# untitled.net
KiCad netlist of a schematic drawn in EAGLE
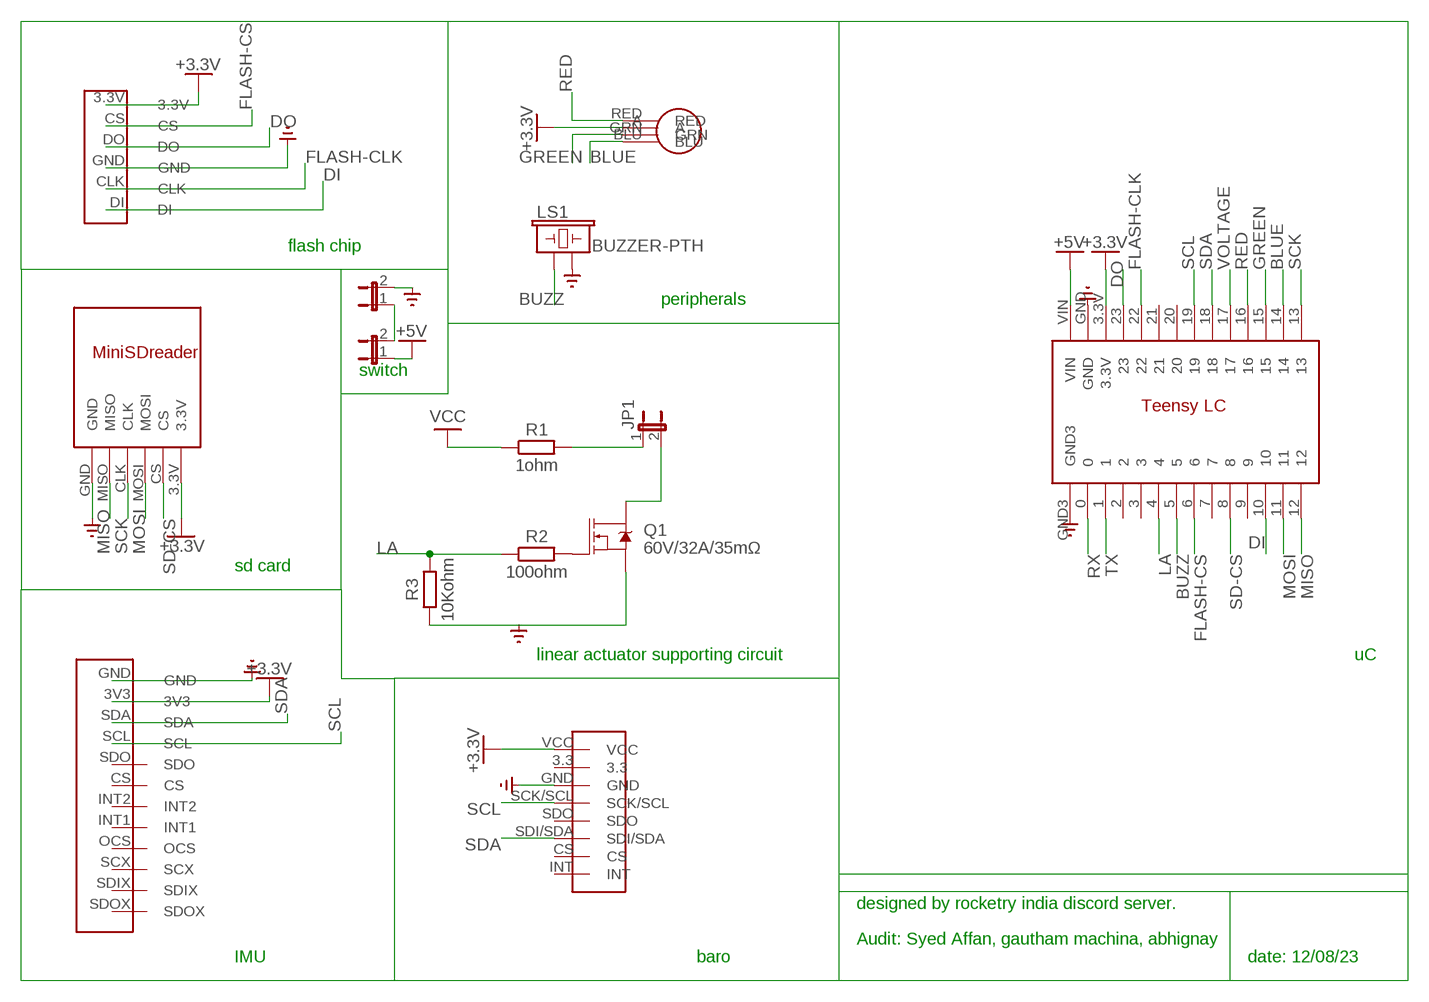
[diagram p0: schematic, sheet 1]

(export (version "E")
  (design (tool "Eeschema 10.0.6"))
  (components
    (comp (ref "JP1")
      (value "JP1E")
      (footprint "eagle-import:JP1")
      (libsource (lib "eagle-import") (part "JP1E"))
    )
    (comp (ref "JP2")
      (value "JP1E")
      (footprint "eagle-import:JP1")
      (libsource (lib "eagle-import") (part "JP1E"))
    )
    (comp (ref "JP3")
      (value "JP1E")
      (footprint "eagle-import:JP1")
      (libsource (lib "eagle-import") (part "JP1E"))
    )
    (comp (ref "LS1")
      (value "BUZZER-PTH")
      (footprint "eagle-import:BUZZER-12MM")
      (libsource (lib "eagle-import") (part "BUZZER-PTH"))
    )
    (comp (ref "Q1")
      (value "60V/32A/35mΩ")
      (footprint "eagle-import:TO220V")
      (libsource (lib "eagle-import") (part "MOSFET-NCH-FQP30N06L"))
    )
    (comp (ref "R1")
      (value "1ohm")
      (footprint "eagle-import:RESAD724W46L381D178B")
      (libsource (lib "eagle-import") (part "RAXIAL-7.2MM-PITCH_"))
    )
    (comp (ref "R2")
      (value "100ohm")
      (footprint "eagle-import:RESAD724W46L381D178B")
      (libsource (lib "eagle-import") (part "RAXIAL-7.2MM-PITCH_"))
    )
    (comp (ref "R3")
      (value "10Kohm")
      (footprint "eagle-import:RESAD724W46L381D178B")
      (libsource (lib "eagle-import") (part "RAXIAL-7.2MM-PITCH_"))
    )
    (comp (ref "U$1")
      (value "TEENSYLC")
      (footprint "eagle-import:TEENSYLC")
      (libsource (lib "eagle-import") (part "TEENSYLC"))
    )
    (comp (ref "U$2")
      (value "LED")
      (footprint "eagle-import:LED")
      (libsource (lib "eagle-import") (part "LED"))
    )
    (comp (ref "U$3")
      (value "FLASH")
      (footprint "eagle-import:FLASH")
      (libsource (lib "eagle-import") (part "FLASH"))
    )
    (comp (ref "U$4")
      (value "MINISDREADER")
      (footprint "eagle-import:MINISDREADER")
      (libsource (lib "eagle-import") (part "MINISDREADER"))
    )
    (comp (ref "U$5")
      (value "LSM6DSO")
      (footprint "eagle-import:LSM6DSO")
      (libsource (lib "eagle-import") (part "LSM6DSO"))
    )
    (comp (ref "U$6")
      (value "BMP390")
      (footprint "eagle-import:BMP390")
      (libsource (lib "eagle-import") (part "BMP390"))
    )
  )
  (nets
    (net (code "1") (name "+3.3V") (class "Default")
      (node (ref "U$1") (pin "3.3V") (pinfunction "3.3V_3.3V") (pintype "bidirectional"))
      (node (ref "U$2") (pin "A") (pinfunction "A_A") (pintype "bidirectional"))
      (node (ref "U$3") (pin "3.3V") (pinfunction "3.3V_3.3V") (pintype "bidirectional"))
      (node (ref "U$4") (pin "3.3V") (pinfunction "3.3V_3.3V") (pintype "bidirectional"))
      (node (ref "U$5") (pin "3V3") (pinfunction "3V3_3V3") (pintype "bidirectional"))
      (node (ref "U$6") (pin "VCC") (pinfunction "VCC_VCC") (pintype "bidirectional"))
    )
    (net (code "2") (name "+5V") (class "Default")
      (node (ref "JP3") (pin "1") (pinfunction "1_1") (pintype "passive"))
      (node (ref "U$1") (pin "VIN") (pinfunction "VIN_VIN") (pintype "bidirectional"))
    )
    (net (code "3") (name "/BLUE") (class "Default")
      (node (ref "U$1") (pin "14") (pinfunction "14_14") (pintype "bidirectional"))
      (node (ref "U$2") (pin "BLU") (pinfunction "BLU_BLU") (pintype "bidirectional"))
    )
    (net (code "4") (name "/BUZZ") (class "Default")
      (node (ref "LS1") (pin "+") (pinfunction "1_+") (pintype "passive"))
      (node (ref "U$1") (pin "5") (pinfunction "5_5") (pintype "bidirectional"))
    )
    (net (code "5") (name "/DI") (class "Default")
      (node (ref "U$1") (pin "10") (pinfunction "10_10") (pintype "bidirectional"))
      (node (ref "U$3") (pin "DI") (pinfunction "DI_DI") (pintype "bidirectional"))
    )
    (net (code "6") (name "/DO") (class "Default")
      (node (ref "U$1") (pin "23") (pinfunction "23_23") (pintype "bidirectional"))
      (node (ref "U$3") (pin "DO") (pinfunction "DO_DO") (pintype "bidirectional"))
    )
    (net (code "7") (name "/FLASH-CLK") (class "Default")
      (node (ref "U$1") (pin "22") (pinfunction "22_22") (pintype "bidirectional"))
      (node (ref "U$3") (pin "CLK") (pinfunction "CLK_CLK") (pintype "bidirectional"))
    )
    (net (code "8") (name "/FLASH-CS") (class "Default")
      (node (ref "U$1") (pin "6") (pinfunction "6_6") (pintype "bidirectional"))
      (node (ref "U$3") (pin "CS") (pinfunction "CS_CS") (pintype "bidirectional"))
    )
    (net (code "9") (name "/GREEN") (class "Default")
      (node (ref "U$1") (pin "15") (pinfunction "15_15") (pintype "bidirectional"))
      (node (ref "U$2") (pin "GRN") (pinfunction "GRN_GRN") (pintype "bidirectional"))
    )
    (net (code "10") (name "/LA") (class "Default")
      (node (ref "R2") (pin "1") (pinfunction "1_1") (pintype "passive"))
      (node (ref "R3") (pin "2") (pinfunction "2_2") (pintype "passive"))
      (node (ref "U$1") (pin "4") (pinfunction "4_4") (pintype "bidirectional"))
    )
    (net (code "11") (name "/MISO") (class "Default")
      (node (ref "U$1") (pin "12") (pinfunction "12_12") (pintype "bidirectional"))
      (node (ref "U$4") (pin "MISO") (pinfunction "MISO_MISO") (pintype "bidirectional"))
    )
    (net (code "12") (name "/MOSI") (class "Default")
      (node (ref "U$1") (pin "11") (pinfunction "11_11") (pintype "bidirectional"))
      (node (ref "U$4") (pin "MOSI") (pinfunction "MOSI_MOSI") (pintype "bidirectional"))
    )
    (net (code "13") (name "/RED") (class "Default")
      (node (ref "U$1") (pin "16") (pinfunction "16_16") (pintype "bidirectional"))
      (node (ref "U$2") (pin "RED") (pinfunction "RED_RED") (pintype "bidirectional"))
    )
    (net (code "14") (name "/RX") (class "Default")
      (node (ref "U$1") (pin "0") (pinfunction "0_0") (pintype "bidirectional"))
    )
    (net (code "15") (name "/SCK") (class "Default")
      (node (ref "U$1") (pin "13") (pinfunction "13_13") (pintype "bidirectional"))
      (node (ref "U$4") (pin "CLK") (pinfunction "CLK_CLK") (pintype "bidirectional"))
    )
    (net (code "16") (name "/SCL") (class "Default")
      (node (ref "U$1") (pin "19") (pinfunction "19_19") (pintype "bidirectional"))
      (node (ref "U$5") (pin "SCL") (pinfunction "SCL_SCL") (pintype "bidirectional"))
      (node (ref "U$6") (pin "SCK/SCL") (pinfunction "SCK/SCL_SCK/SCL") (pintype "bidirectional"))
    )
    (net (code "17") (name "/SD-CS") (class "Default")
      (node (ref "U$1") (pin "8") (pinfunction "8_8") (pintype "bidirectional"))
      (node (ref "U$4") (pin "CS") (pinfunction "CS_CS") (pintype "bidirectional"))
    )
    (net (code "18") (name "/SDA") (class "Default")
      (node (ref "U$1") (pin "18") (pinfunction "18_18") (pintype "bidirectional"))
      (node (ref "U$5") (pin "SDA") (pinfunction "SDA_SDA") (pintype "bidirectional"))
      (node (ref "U$6") (pin "SDI/SDA") (pinfunction "SDI/SDA_SDI/SDA") (pintype "bidirectional"))
    )
    (net (code "19") (name "/TX") (class "Default")
      (node (ref "U$1") (pin "1") (pinfunction "1_1") (pintype "bidirectional"))
    )
    (net (code "20") (name "/VOLTAGE") (class "Default")
      (node (ref "U$1") (pin "17") (pinfunction "17_17") (pintype "bidirectional"))
    )
    (net (code "21") (name "Net-(JP1-Pad1)") (class "Default")
      (node (ref "JP1") (pin "1") (pinfunction "1_1") (pintype "passive"))
      (node (ref "R1") (pin "2") (pinfunction "2_2") (pintype "passive"))
    )
    (net (code "22") (name "Net-(JP2-Pad1)") (class "Default")
      (node (ref "JP2") (pin "1") (pinfunction "1_1") (pintype "passive"))
      (node (ref "JP3") (pin "2") (pinfunction "2_2") (pintype "passive"))
    )
    (net (code "23") (name "Net-(Q1-D)") (class "Default")
      (node (ref "JP1") (pin "2") (pinfunction "2_2") (pintype "passive"))
      (node (ref "Q1") (pin "2") (pinfunction "D_2") (pintype "bidirectional"))
    )
    (net (code "24") (name "Net-(Q1-G)") (class "Default")
      (node (ref "Q1") (pin "1") (pinfunction "G_1") (pintype "bidirectional"))
      (node (ref "R2") (pin "2") (pinfunction "2_2") (pintype "passive"))
    )
    (net (code "25") (name "Net-(Q1-S)") (class "Default")
      (node (ref "Q1") (pin "3") (pinfunction "S_3") (pintype "bidirectional"))
      (node (ref "R3") (pin "1") (pinfunction "1_1") (pintype "passive"))
    )
    (net (code "26") (name "SUPPLY0_GND_") (class "Default")
      (node (ref "JP2") (pin "2") (pinfunction "2_2") (pintype "passive"))
      (node (ref "U$1") (pin "GND") (pinfunction "GND_GND") (pintype "bidirectional"))
      (node (ref "U$3") (pin "GND") (pinfunction "GND_GND") (pintype "bidirectional"))
      (node (ref "U$4") (pin "GND") (pinfunction "GND_GND") (pintype "bidirectional"))
      (node (ref "U$5") (pin "GND") (pinfunction "GND_GND") (pintype "bidirectional"))
      (node (ref "U$6") (pin "GND") (pinfunction "GND_GND") (pintype "bidirectional"))
    )
    (net (code "27") (name "VCC") (class "Default")
      (node (ref "R1") (pin "1") (pinfunction "1_1") (pintype "passive"))
    )
    (net (code "28") (name "unconnected-(LS1-2-Pad-)") (class "Default")
      (node (ref "LS1") (pin "-") (pinfunction "2_-") (pintype "passive"))
    )
    (net (code "29") (name "unconnected-(U$1-Pad2)") (class "Default")
      (node (ref "U$1") (pin "2") (pinfunction "2_2") (pintype "bidirectional"))
    )
    (net (code "30") (name "unconnected-(U$1-Pad3)") (class "Default")
      (node (ref "U$1") (pin "3") (pinfunction "3_3") (pintype "bidirectional"))
    )
    (net (code "31") (name "unconnected-(U$1-Pad7)") (class "Default")
      (node (ref "U$1") (pin "7") (pinfunction "7_7") (pintype "bidirectional"))
    )
    (net (code "32") (name "unconnected-(U$1-Pad9)") (class "Default")
      (node (ref "U$1") (pin "9") (pinfunction "9_9") (pintype "bidirectional"))
    )
    (net (code "33") (name "unconnected-(U$1-Pad20)") (class "Default")
      (node (ref "U$1") (pin "20") (pinfunction "20_20") (pintype "bidirectional"))
    )
    (net (code "34") (name "unconnected-(U$1-Pad21)") (class "Default")
      (node (ref "U$1") (pin "21") (pinfunction "21_21") (pintype "bidirectional"))
    )
    (net (code "35") (name "unconnected-(U$1-PadGND3)") (class "Default")
      (node (ref "U$1") (pin "GND3") (pinfunction "GND3_GND3") (pintype "bidirectional"))
    )
    (net (code "36") (name "unconnected-(U$5-PadCS)") (class "Default")
      (node (ref "U$5") (pin "CS") (pinfunction "CS_CS") (pintype "bidirectional"))
    )
    (net (code "37") (name "unconnected-(U$5-PadINT1)") (class "Default")
      (node (ref "U$5") (pin "INT1") (pinfunction "INT1_INT1") (pintype "bidirectional"))
    )
    (net (code "38") (name "unconnected-(U$5-PadINT2)") (class "Default")
      (node (ref "U$5") (pin "INT2") (pinfunction "INT2_INT2") (pintype "bidirectional"))
    )
    (net (code "39") (name "unconnected-(U$5-PadOCS)") (class "Default")
      (node (ref "U$5") (pin "OCS") (pinfunction "OCS_OCS") (pintype "bidirectional"))
    )
    (net (code "40") (name "unconnected-(U$5-PadSCX)") (class "Default")
      (node (ref "U$5") (pin "SCX") (pinfunction "SCX_SCX") (pintype "bidirectional"))
    )
    (net (code "41") (name "unconnected-(U$5-PadSDIX)") (class "Default")
      (node (ref "U$5") (pin "SDIX") (pinfunction "SDIX_SDIX") (pintype "bidirectional"))
    )
    (net (code "42") (name "unconnected-(U$5-PadSDO)") (class "Default")
      (node (ref "U$5") (pin "SDO") (pinfunction "SDO_SDO") (pintype "bidirectional"))
    )
    (net (code "43") (name "unconnected-(U$5-PadSDOX)") (class "Default")
      (node (ref "U$5") (pin "SDOX") (pinfunction "SDOX_SDOX") (pintype "bidirectional"))
    )
    (net (code "44") (name "unconnected-(U$6-Pad3.3)") (class "Default")
      (node (ref "U$6") (pin "3.3") (pinfunction "3.3_3.3") (pintype "bidirectional"))
    )
    (net (code "45") (name "unconnected-(U$6-PadCS)") (class "Default")
      (node (ref "U$6") (pin "CS") (pinfunction "CS_CS") (pintype "bidirectional"))
    )
    (net (code "46") (name "unconnected-(U$6-PadINT)") (class "Default")
      (node (ref "U$6") (pin "INT") (pinfunction "INT_INT") (pintype "bidirectional"))
    )
    (net (code "47") (name "unconnected-(U$6-PadSDO)") (class "Default")
      (node (ref "U$6") (pin "SDO") (pinfunction "SDO_SDO") (pintype "bidirectional"))
    )
  )
)
